# Untitled.net
KiCad netlist of a schematic drawn in EAGLE
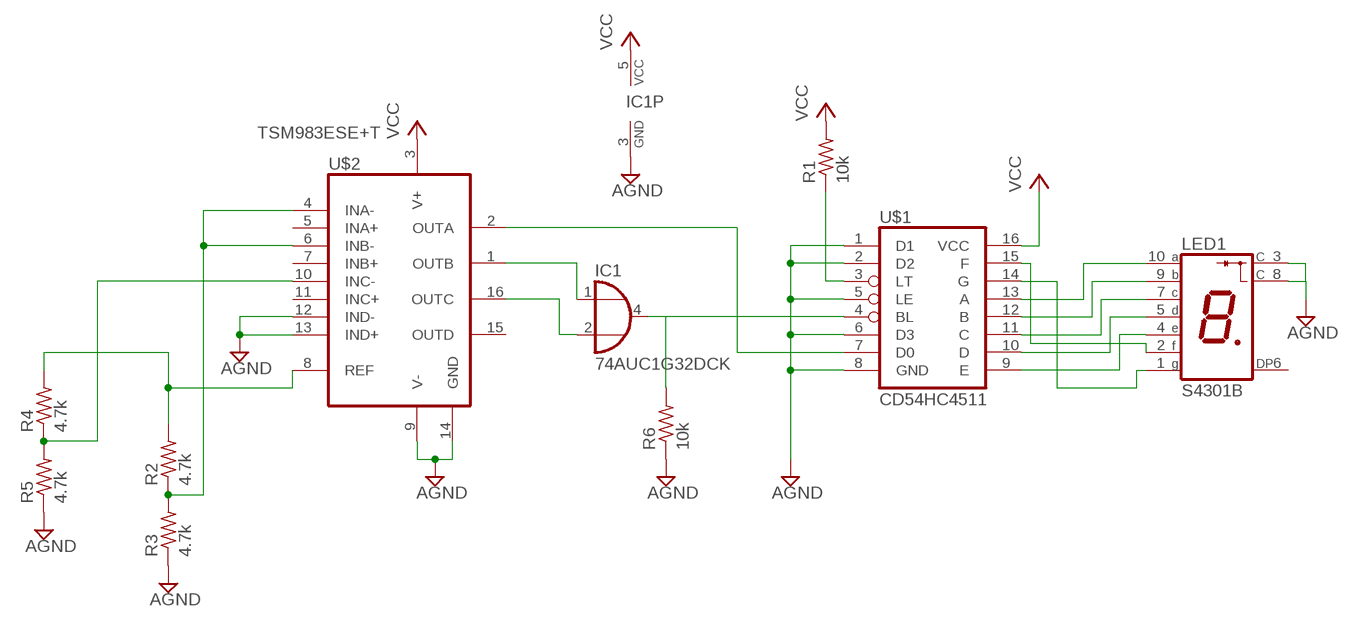
[diagram p0: schematic, sheet 1]

(export (version "E")
  (design (tool "Eeschema 10.0.6"))
  (components
    (comp (ref "IC1")
      (value "74AUC1G32DCK")
      (footprint "eagle-import:SC70-5")
      (libsource (lib "eagle-import") (part "741G32DCKAUC"))
    )
    (comp (ref "LED1")
      (value "S4301B")
      (footprint "eagle-import:S4301B")
      (libsource (lib "eagle-import") (part "S4301B"))
    )
    (comp (ref "R1")
      (value "10k")
      (footprint "eagle-import:R1206")
      (libsource (lib "eagle-import") (part "R-US_R1206"))
    )
    (comp (ref "R2")
      (value "4.7k")
      (footprint "eagle-import:R1206")
      (libsource (lib "eagle-import") (part "R-US_R1206"))
    )
    (comp (ref "R3")
      (value "4.7k")
      (footprint "eagle-import:R1206")
      (libsource (lib "eagle-import") (part "R-US_R1206"))
    )
    (comp (ref "R4")
      (value "4.7k")
      (footprint "eagle-import:R1206")
      (libsource (lib "eagle-import") (part "R-US_R1206"))
    )
    (comp (ref "R5")
      (value "4.7k")
      (footprint "eagle-import:R1206")
      (libsource (lib "eagle-import") (part "R-US_R1206"))
    )
    (comp (ref "R6")
      (value "10k")
      (footprint "eagle-import:R1206")
      (libsource (lib "eagle-import") (part "R-US_R1206"))
    )
    (comp (ref "U$1")
      (value "CD54HC4511")
      (footprint "eagle-import:CD54HC4511")
      (libsource (lib "eagle-import") (part "CD54HC4511"))
    )
    (comp (ref "U$2")
      (value "TSM983ESE+T")
      (footprint "eagle-import:TSM983ESE+T")
      (libsource (lib "eagle-import") (part "TSM983ESE+T"))
    )
  )
  (nets
    (net (code "1") (name "AGND") (class "Default")
      (node (ref "IC1") (pin "3") (pinfunction "GND_3") (pintype "power_in"))
      (node (ref "LED1") (pin "3") (pinfunction "C_3") (pintype "passive"))
      (node (ref "LED1") (pin "8") (pinfunction "C_8") (pintype "passive"))
      (node (ref "R3") (pin "1") (pinfunction "1_1") (pintype "passive"))
      (node (ref "R5") (pin "1") (pinfunction "1_1") (pintype "passive"))
      (node (ref "R6") (pin "1") (pinfunction "1_1") (pintype "passive"))
      (node (ref "U$1") (pin "1") (pinfunction "D1_1") (pintype "bidirectional"))
      (node (ref "U$1") (pin "2") (pinfunction "D2_2") (pintype "input"))
      (node (ref "U$1") (pin "5") (pinfunction "LE_5") (pintype "input"))
      (node (ref "U$1") (pin "6") (pinfunction "D3_6") (pintype "input"))
      (node (ref "U$1") (pin "8") (pinfunction "GND_8") (pintype "input"))
      (node (ref "U$2") (pin "12") (pinfunction "IND-_12") (pintype "input"))
      (node (ref "U$2") (pin "13") (pinfunction "IND+_13") (pintype "input"))
      (node (ref "U$2") (pin "14") (pinfunction "GND_14") (pintype "bidirectional"))
      (node (ref "U$2") (pin "9") (pinfunction "V-_9") (pintype "input"))
    )
    (net (code "2") (name "Net-(IC1A-I0)") (class "Default")
      (node (ref "IC1") (pin "1") (pinfunction "I0_1") (pintype "input"))
      (node (ref "U$2") (pin "1") (pinfunction "OUTB_1") (pintype "output"))
    )
    (net (code "3") (name "Net-(IC1A-I1)") (class "Default")
      (node (ref "IC1") (pin "2") (pinfunction "I1_2") (pintype "input"))
      (node (ref "U$2") (pin "16") (pinfunction "OUTC_16") (pintype "output"))
    )
    (net (code "4") (name "Net-(IC1A-O)") (class "Default")
      (node (ref "IC1") (pin "4") (pinfunction "O_4") (pintype "output"))
      (node (ref "R6") (pin "2") (pinfunction "2_2") (pintype "passive"))
      (node (ref "U$1") (pin "4") (pinfunction "BL_4") (pintype "input"))
    )
    (net (code "5") (name "Net-(LED1-A)") (class "Default")
      (node (ref "LED1") (pin "10") (pinfunction "A_10") (pintype "passive"))
      (node (ref "U$1") (pin "13") (pinfunction "A_13") (pintype "bidirectional"))
    )
    (net (code "6") (name "Net-(LED1-B)") (class "Default")
      (node (ref "LED1") (pin "9") (pinfunction "B_9") (pintype "passive"))
      (node (ref "U$1") (pin "12") (pinfunction "B_12") (pintype "output"))
    )
    (net (code "7") (name "Net-(LED1-D)") (class "Default")
      (node (ref "LED1") (pin "5") (pinfunction "D_5") (pintype "passive"))
      (node (ref "U$1") (pin "10") (pinfunction "D_10") (pintype "output"))
    )
    (net (code "8") (name "Net-(LED1-E)") (class "Default")
      (node (ref "LED1") (pin "4") (pinfunction "E_4") (pintype "passive"))
      (node (ref "U$1") (pin "9") (pinfunction "E_9") (pintype "output"))
    )
    (net (code "9") (name "Net-(LED1-F)") (class "Default")
      (node (ref "LED1") (pin "2") (pinfunction "F_2") (pintype "passive"))
      (node (ref "U$1") (pin "15") (pinfunction "F_15") (pintype "output"))
    )
    (net (code "10") (name "Net-(LED1-G)") (class "Default")
      (node (ref "LED1") (pin "1") (pinfunction "G_1") (pintype "passive"))
      (node (ref "U$1") (pin "14") (pinfunction "G_14") (pintype "output"))
    )
    (net (code "11") (name "Net-(U$1-C)") (class "Default")
      (node (ref "LED1") (pin "7") (pinfunction "C_7") (pintype "passive"))
      (node (ref "U$1") (pin "11") (pinfunction "C_11") (pintype "output"))
    )
    (net (code "12") (name "Net-(U$1-D0)") (class "Default")
      (node (ref "U$1") (pin "7") (pinfunction "D0_7") (pintype "input"))
      (node (ref "U$2") (pin "2") (pinfunction "OUTA_2") (pintype "output"))
    )
    (net (code "13") (name "Net-(U$1-LT)") (class "Default")
      (node (ref "R1") (pin "1") (pinfunction "1_1") (pintype "passive"))
      (node (ref "U$1") (pin "3") (pinfunction "LT_3") (pintype "input"))
    )
    (net (code "14") (name "Net-(U$2-INA-)") (class "Default")
      (node (ref "R2") (pin "1") (pinfunction "1_1") (pintype "passive"))
      (node (ref "R3") (pin "2") (pinfunction "2_2") (pintype "passive"))
      (node (ref "U$2") (pin "4") (pinfunction "INA-_4") (pintype "input"))
      (node (ref "U$2") (pin "6") (pinfunction "INB-_6") (pintype "input"))
    )
    (net (code "15") (name "Net-(U$2-INC-)") (class "Default")
      (node (ref "R4") (pin "1") (pinfunction "1_1") (pintype "passive"))
      (node (ref "R5") (pin "2") (pinfunction "2_2") (pintype "passive"))
      (node (ref "U$2") (pin "10") (pinfunction "INC-_10") (pintype "input"))
    )
    (net (code "16") (name "Net-(U$2-REF)") (class "Default")
      (node (ref "R2") (pin "2") (pinfunction "2_2") (pintype "passive"))
      (node (ref "R4") (pin "2") (pinfunction "2_2") (pintype "passive"))
      (node (ref "U$2") (pin "8") (pinfunction "REF_8") (pintype "input"))
    )
    (net (code "17") (name "VCC") (class "Default")
      (node (ref "IC1") (pin "5") (pinfunction "VCC_5") (pintype "power_in"))
      (node (ref "R1") (pin "2") (pinfunction "2_2") (pintype "passive"))
      (node (ref "U$1") (pin "16") (pinfunction "VCC_16") (pintype "output"))
      (node (ref "U$2") (pin "3") (pinfunction "V+_3") (pintype "input"))
    )
    (net (code "18") (name "unconnected-(LED1-DP-Pad6)") (class "Default")
      (node (ref "LED1") (pin "6") (pinfunction "DP_6") (pintype "passive"))
    )
    (net (code "19") (name "unconnected-(U$2-INA+-Pad5)") (class "Default")
      (node (ref "U$2") (pin "5") (pinfunction "INA+_5") (pintype "input"))
    )
    (net (code "20") (name "unconnected-(U$2-INB+-Pad7)") (class "Default")
      (node (ref "U$2") (pin "7") (pinfunction "INB+_7") (pintype "input"))
    )
    (net (code "21") (name "unconnected-(U$2-INC+-Pad11)") (class "Default")
      (node (ref "U$2") (pin "11") (pinfunction "INC+_11") (pintype "input"))
    )
    (net (code "22") (name "unconnected-(U$2-OUTD-Pad15)") (class "Default")
      (node (ref "U$2") (pin "15") (pinfunction "OUTD_15") (pintype "bidirectional"))
    )
  )
)
